# MCU.net
KiCad netlist of a schematic drawn in Altium Designer
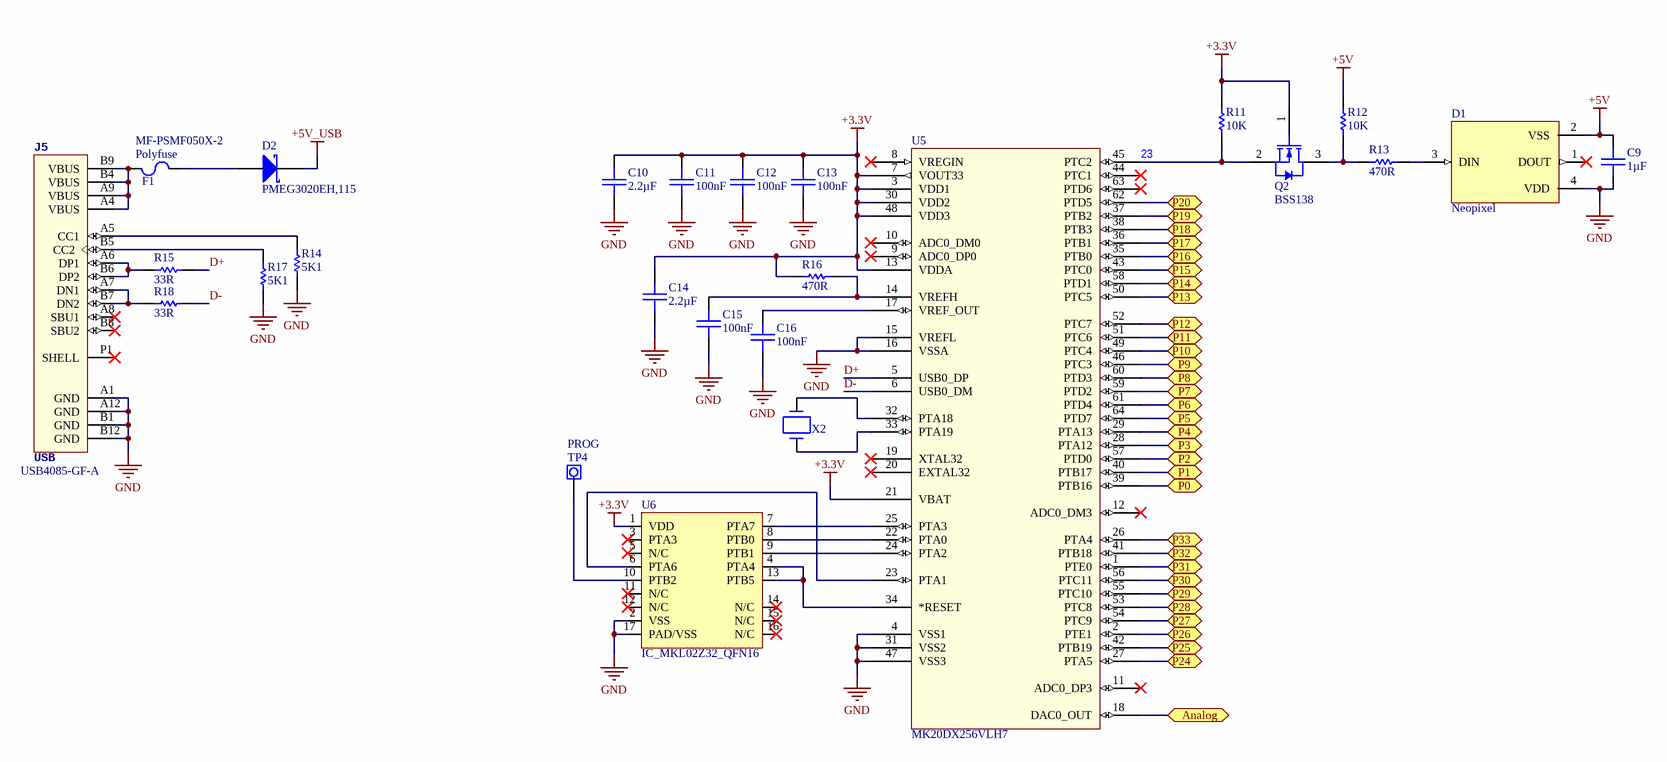
[diagram p0: MCU.SchDoc]

(export (version "E")
  (design (tool "Eeschema 10.0.6"))
  (components
    (comp (ref "C9")
      (value "1µF")
      (footprint "0603_CAP")
      (libsource (lib "Moonlight-Components") (part "Capacitor"))
    )
    (comp (ref "C10")
      (value "2.2µF")
      (footprint "0603_CAP")
      (libsource (lib "Moonlight-Components") (part "Capacitor"))
    )
    (comp (ref "C11")
      (value "100nF")
      (footprint "0603_CAP")
      (libsource (lib "Moonlight-Components") (part "Capacitor"))
    )
    (comp (ref "C12")
      (value "100nF")
      (footprint "0603_CAP")
      (libsource (lib "Moonlight-Components") (part "Capacitor"))
    )
    (comp (ref "C13")
      (value "100nF")
      (footprint "0603_CAP")
      (libsource (lib "Moonlight-Components") (part "Capacitor"))
    )
    (comp (ref "C14")
      (value "2.2µF")
      (footprint "0603_CAP")
      (libsource (lib "Moonlight-Components") (part "Capacitor"))
    )
    (comp (ref "C15")
      (value "100nF")
      (footprint "0603_CAP")
      (libsource (lib "Moonlight-Components") (part "Capacitor"))
    )
    (comp (ref "C16")
      (value "100nF")
      (footprint "0603_CAP")
      (libsource (lib "Moonlight-Components") (part "Capacitor"))
    )
    (comp (ref "D1")
      (value "Neopixel")
      (footprint "2659")
      (description "Adafruit Neopixel SMD 3535\r\nAdafruit part no. 2659\r\nDigikey part no. 1528-1542-ND")
      (fields (field (name "MP") "2659") (field (name "MF") "Adafruit Industries"))
      (libsource (lib "Moonlight-Components") (part "Neopixel"))
    )
    (comp (ref "D2")
      (value "PMEG3020EH,115")
      (footprint "SOD-123")
      (description "Digikey part no. 1727-3873-1-ND")
      (libsource (lib "Moonlight-Components") (part "Schottky diode"))
    )
    (comp (ref "F1")
      (value "Polyfuse")
      (footprint "0805")
      (description "MF-PSMF050X-2\r\nDigikey part no. MF-PSMF050X-2CT-ND")
      (libsource (lib "Moonlight-Components") (part "Fuse"))
    )
    (comp (ref "J5")
      (value "USB")
      (footprint "GCT_USB4085-GF-A_REVA")
      (description "USB 2.0 Type C Receptacle Dip Type, PCB Top Mount\r\n(Digikey part no. 2073-USB4085-GF-ACT-ND)")
      (fields (field (name "MANUFACTURER") "Global Connector Technology"))
      (libsource (lib "Moonlight-Components") (part "USB4085-GF-A_revA"))
    )
    (comp (ref "Q2")
      (value "BSS138")
      (footprint "INTR-SOT-23-3_V")
      (description "N-MOS transistor\r\nDigikey part no. BSS138CT-ND")
      (fields (field (name "MANUFACTURER") "International Rectifier"))
      (libsource (lib "Moonlight-Components") (part "IRLML2502TRPBF"))
    )
    (comp (ref "R11")
      (value "10K")
      (footprint "0603_RES")
      (libsource (lib "Moonlight-Components") (part "Resistor"))
    )
    (comp (ref "R12")
      (value "10K")
      (footprint "0603_RES")
      (libsource (lib "Moonlight-Components") (part "Resistor"))
    )
    (comp (ref "R13")
      (value "470R")
      (footprint "0603_RES")
      (libsource (lib "Moonlight-Components") (part "Resistor"))
    )
    (comp (ref "R14")
      (value "5K1")
      (footprint "0603_RES")
      (libsource (lib "Moonlight-Components") (part "Resistor"))
    )
    (comp (ref "R15")
      (value "33R")
      (footprint "0603_RES")
      (libsource (lib "Moonlight-Components") (part "Resistor"))
    )
    (comp (ref "R16")
      (value "470R")
      (footprint "0603_RES")
      (libsource (lib "Moonlight-Components") (part "Resistor"))
    )
    (comp (ref "R17")
      (value "5K1")
      (footprint "0603_RES")
      (libsource (lib "Moonlight-Components") (part "Resistor"))
    )
    (comp (ref "R18")
      (value "33R")
      (footprint "0603_RES")
      (libsource (lib "Moonlight-Components") (part "Resistor"))
    )
    (comp (ref "TP4")
      (value "PROG")
      (footprint "Testpoint2")
      (libsource (lib "Moonlight-Components") (part "Testpoint"))
    )
    (comp (ref "U5")
      (value "MK20DX256VLH7")
      (footprint "98ASS23234W_NXP")
      (description "No Description Available")
      (fields (field (name "COPYRIGHT") "Copyright (C) 2016 Accelerated Designs. All rights reserved"))
      (libsource (lib "Moonlight-Components") (part "MK20DX256VLH7"))
    )
    (comp (ref "U6")
      (value "IC_MKL02Z32_QFN16")
      (footprint "QFN50P300X300X65-17N")
      (description "Teensy bootloader")
      (fields (field (name "MP") "MKL02Z32VFG4") (field (name "MF") "NXP USA"))
      (libsource (lib "Moonlight-Components") (part "IC_MKL02Z32_QFN16"))
    )
    (comp (ref "X2")
      (value "NX3225SA-16.000000MHZ-B3")
      (footprint "XTAL_NX3225SA")
      (description "Digikey part no. 644-1099-1-ND")
      (libsource (lib "Moonlight-Components") (part "XTAL_16 MHz"))
    )
  )
  (nets
    (net (code "1") (name "+3.3V") (class "Default")
      (node (ref "C10") (pin "1") (pinfunction "1_1") (pintype "passive"))
      (node (ref "C11") (pin "1") (pinfunction "1_1") (pintype "passive"))
      (node (ref "C12") (pin "1") (pinfunction "1_1") (pintype "passive"))
      (node (ref "C13") (pin "1") (pinfunction "1_1") (pintype "passive"))
      (node (ref "C14") (pin "1") (pinfunction "1_1") (pintype "passive"))
      (node (ref "Q2") (pin "1") (pinfunction "G_1") (pintype "passive"))
      (node (ref "R11") (pin "1") (pinfunction "1_1") (pintype "passive"))
      (node (ref "R16") (pin "1") (pinfunction "1_1") (pintype "passive"))
      (node (ref "U5") (pin "13") (pinfunction "VDDA_13") (pintype "power_in"))
      (node (ref "U5") (pin "21") (pinfunction "VBAT_21") (pintype "power_in"))
      (node (ref "U5") (pin "3") (pinfunction "VDD1_3") (pintype "power_in"))
      (node (ref "U5") (pin "30") (pinfunction "VDD2_30") (pintype "power_in"))
      (node (ref "U5") (pin "48") (pinfunction "VDD3_48") (pintype "power_in"))
      (node (ref "U5") (pin "7") (pinfunction "VOUT33_7") (pintype "output"))
      (node (ref "U6") (pin "1") (pinfunction "VDD_1") (pintype "power_in"))
    )
    (net (code "2") (name "+5V") (class "Default")
      (node (ref "C9") (pin "1") (pinfunction "1_1") (pintype "passive"))
      (node (ref "D1") (pin "2") (pinfunction "VSS_2") (pintype "power_in"))
      (node (ref "R12") (pin "1") (pinfunction "1_1") (pintype "passive"))
    )
    (net (code "3") (name "+5V_USB") (class "Default")
      (node (ref "D2") (pin "2") (pinfunction "K_2") (pintype "passive"))
    )
    (net (code "4") (name "/Analog") (class "Default")
      (node (ref "U5") (pin "18") (pinfunction "DAC0_OUT_18") (pintype "bidirectional"))
    )
    (net (code "5") (name "/D+") (class "Default")
      (node (ref "R15") (pin "2") (pinfunction "2_2") (pintype "passive"))
      (node (ref "U5") (pin "5") (pinfunction "USB0_DP_5") (pintype "passive"))
    )
    (net (code "6") (name "/D-") (class "Default")
      (node (ref "R18") (pin "2") (pinfunction "2_2") (pintype "passive"))
      (node (ref "U5") (pin "6") (pinfunction "USB0_DM_6") (pintype "passive"))
    )
    (net (code "7") (name "/P0") (class "Default")
      (node (ref "U5") (pin "39") (pinfunction "PTB16_39") (pintype "bidirectional"))
    )
    (net (code "8") (name "/P1") (class "Default")
      (node (ref "U5") (pin "40") (pinfunction "PTB17_40") (pintype "bidirectional"))
    )
    (net (code "9") (name "/P2") (class "Default")
      (node (ref "U5") (pin "57") (pinfunction "PTD0_57") (pintype "bidirectional"))
    )
    (net (code "10") (name "/P3") (class "Default")
      (node (ref "U5") (pin "28") (pinfunction "PTA12_28") (pintype "bidirectional"))
    )
    (net (code "11") (name "/P4") (class "Default")
      (node (ref "U5") (pin "29") (pinfunction "PTA13_29") (pintype "bidirectional"))
    )
    (net (code "12") (name "/P5") (class "Default")
      (node (ref "U5") (pin "64") (pinfunction "PTD7_64") (pintype "bidirectional"))
    )
    (net (code "13") (name "/P6") (class "Default")
      (node (ref "U5") (pin "61") (pinfunction "PTD4_61") (pintype "bidirectional"))
    )
    (net (code "14") (name "/P7") (class "Default")
      (node (ref "U5") (pin "59") (pinfunction "PTD2_59") (pintype "bidirectional"))
    )
    (net (code "15") (name "/P8") (class "Default")
      (node (ref "U5") (pin "60") (pinfunction "PTD3_60") (pintype "bidirectional"))
    )
    (net (code "16") (name "/P9") (class "Default")
      (node (ref "U5") (pin "46") (pinfunction "PTC3_46") (pintype "bidirectional"))
    )
    (net (code "17") (name "/P10") (class "Default")
      (node (ref "U5") (pin "49") (pinfunction "PTC4_49") (pintype "bidirectional"))
    )
    (net (code "18") (name "/P11") (class "Default")
      (node (ref "U5") (pin "51") (pinfunction "PTC6_51") (pintype "bidirectional"))
    )
    (net (code "19") (name "/P12") (class "Default")
      (node (ref "U5") (pin "52") (pinfunction "PTC7_52") (pintype "bidirectional"))
    )
    (net (code "20") (name "/P13") (class "Default")
      (node (ref "U5") (pin "50") (pinfunction "PTC5_50") (pintype "bidirectional"))
    )
    (net (code "21") (name "/P14") (class "Default")
      (node (ref "U5") (pin "58") (pinfunction "PTD1_58") (pintype "bidirectional"))
    )
    (net (code "22") (name "/P15") (class "Default")
      (node (ref "U5") (pin "43") (pinfunction "PTC0_43") (pintype "bidirectional"))
    )
    (net (code "23") (name "/P16") (class "Default")
      (node (ref "U5") (pin "35") (pinfunction "PTB0_35") (pintype "bidirectional"))
    )
    (net (code "24") (name "/P17") (class "Default")
      (node (ref "U5") (pin "36") (pinfunction "PTB1_36") (pintype "bidirectional"))
    )
    (net (code "25") (name "/P18") (class "Default")
      (node (ref "U5") (pin "38") (pinfunction "PTB3_38") (pintype "bidirectional"))
    )
    (net (code "26") (name "/P19") (class "Default")
      (node (ref "U5") (pin "37") (pinfunction "PTB2_37") (pintype "bidirectional"))
    )
    (net (code "27") (name "/P20") (class "Default")
      (node (ref "U5") (pin "62") (pinfunction "PTD5_62") (pintype "bidirectional"))
    )
    (net (code "28") (name "/P24") (class "Default")
      (node (ref "U5") (pin "27") (pinfunction "PTA5_27") (pintype "bidirectional"))
    )
    (net (code "29") (name "/P25") (class "Default")
      (node (ref "U5") (pin "42") (pinfunction "PTB19_42") (pintype "bidirectional"))
    )
    (net (code "30") (name "/P26") (class "Default")
      (node (ref "U5") (pin "2") (pinfunction "PTE1_2") (pintype "bidirectional"))
    )
    (net (code "31") (name "/P27") (class "Default")
      (node (ref "U5") (pin "54") (pinfunction "PTC9_54") (pintype "bidirectional"))
    )
    (net (code "32") (name "/P28") (class "Default")
      (node (ref "U5") (pin "53") (pinfunction "PTC8_53") (pintype "bidirectional"))
    )
    (net (code "33") (name "/P29") (class "Default")
      (node (ref "U5") (pin "55") (pinfunction "PTC10_55") (pintype "bidirectional"))
    )
    (net (code "34") (name "/P30") (class "Default")
      (node (ref "U5") (pin "56") (pinfunction "PTC11_56") (pintype "bidirectional"))
    )
    (net (code "35") (name "/P31") (class "Default")
      (node (ref "U5") (pin "1") (pinfunction "PTE0_1") (pintype "bidirectional"))
    )
    (net (code "36") (name "/P32") (class "Default")
      (node (ref "U5") (pin "41") (pinfunction "PTB18_41") (pintype "bidirectional"))
    )
    (net (code "37") (name "/P33") (class "Default")
      (node (ref "U5") (pin "26") (pinfunction "PTA4_26") (pintype "bidirectional"))
    )
    (net (code "38") (name "GND") (class "Default")
      (node (ref "C10") (pin "2") (pinfunction "2_2") (pintype "passive"))
      (node (ref "C11") (pin "2") (pinfunction "2_2") (pintype "passive"))
      (node (ref "C12") (pin "2") (pinfunction "2_2") (pintype "passive"))
      (node (ref "C13") (pin "2") (pinfunction "2_2") (pintype "passive"))
      (node (ref "C14") (pin "2") (pinfunction "2_2") (pintype "passive"))
      (node (ref "C15") (pin "2") (pinfunction "2_2") (pintype "passive"))
      (node (ref "C16") (pin "2") (pinfunction "2_2") (pintype "passive"))
      (node (ref "C9") (pin "2") (pinfunction "2_2") (pintype "passive"))
      (node (ref "D1") (pin "4") (pinfunction "VDD_4") (pintype "power_in"))
      (node (ref "J5") (pin "A1") (pinfunction "GND_A1") (pintype "power_in"))
      (node (ref "J5") (pin "A12") (pinfunction "GND_A12") (pintype "power_in"))
      (node (ref "J5") (pin "B1") (pinfunction "GND_B1") (pintype "passive"))
      (node (ref "J5") (pin "B12") (pinfunction "GND_B12") (pintype "power_in"))
      (node (ref "R14") (pin "2") (pinfunction "2_2") (pintype "passive"))
      (node (ref "R17") (pin "1") (pinfunction "1_1") (pintype "passive"))
      (node (ref "U5") (pin "15") (pinfunction "VREFL_15") (pintype "power_in"))
      (node (ref "U5") (pin "16") (pinfunction "VSSA_16") (pintype "power_in"))
      (node (ref "U5") (pin "31") (pinfunction "VSS2_31") (pintype "power_in"))
      (node (ref "U5") (pin "4") (pinfunction "VSS1_4") (pintype "power_in"))
      (node (ref "U5") (pin "47") (pinfunction "VSS3_47") (pintype "power_in"))
      (node (ref "U6") (pin "17") (pinfunction "PAD/VSS_17") (pintype "power_in"))
      (node (ref "U6") (pin "2") (pinfunction "VSS_2") (pintype "power_in"))
    )
    (net (code "39") (name "Net-(D1-DIN)") (class "Default")
      (node (ref "D1") (pin "3") (pinfunction "DIN_3") (pintype "input"))
      (node (ref "R13") (pin "2") (pinfunction "2_2") (pintype "passive"))
    )
    (net (code "40") (name "Net-(D2-A)") (class "Default")
      (node (ref "D2") (pin "1") (pinfunction "A_1") (pintype "passive"))
      (node (ref "F1") (pin "2") (pinfunction "2_2") (pintype "passive"))
    )
    (net (code "41") (name "Net-(F1-Pad1)") (class "Default")
      (node (ref "F1") (pin "1") (pinfunction "1_1") (pintype "passive"))
      (node (ref "J5") (pin "A4") (pinfunction "VBUS_A4") (pintype "power_in"))
      (node (ref "J5") (pin "A9") (pinfunction "VBUS_A9") (pintype "power_in"))
      (node (ref "J5") (pin "B4") (pinfunction "VBUS_B4") (pintype "power_in"))
      (node (ref "J5") (pin "B9") (pinfunction "VBUS_B9") (pintype "power_in"))
    )
    (net (code "42") (name "Net-(J5-CC1)") (class "Default")
      (node (ref "J5") (pin "A5") (pinfunction "CC1_A5") (pintype "bidirectional"))
      (node (ref "R14") (pin "1") (pinfunction "1_1") (pintype "passive"))
    )
    (net (code "43") (name "Net-(J5-CC2)") (class "Default")
      (node (ref "J5") (pin "B5") (pinfunction "CC2_B5") (pintype "bidirectional"))
      (node (ref "R17") (pin "2") (pinfunction "2_2") (pintype "passive"))
    )
    (net (code "44") (name "Net-(J5-DN1)") (class "Default")
      (node (ref "J5") (pin "A7") (pinfunction "DN1_A7") (pintype "bidirectional"))
      (node (ref "J5") (pin "B7") (pinfunction "DN2_B7") (pintype "bidirectional"))
      (node (ref "R18") (pin "1") (pinfunction "1_1") (pintype "passive"))
    )
    (net (code "45") (name "Net-(J5-DP1)") (class "Default")
      (node (ref "J5") (pin "A6") (pinfunction "DP1_A6") (pintype "bidirectional"))
      (node (ref "J5") (pin "B6") (pinfunction "DP2_B6") (pintype "bidirectional"))
      (node (ref "R15") (pin "1") (pinfunction "1_1") (pintype "passive"))
    )
    (net (code "46") (name "Net-(Q2-D)") (class "Default")
      (node (ref "Q2") (pin "3") (pinfunction "D_3") (pintype "passive"))
      (node (ref "R12") (pin "2") (pinfunction "2_2") (pintype "passive"))
      (node (ref "R13") (pin "1") (pinfunction "1_1") (pintype "passive"))
    )
    (net (code "47") (name "Net-(Q2-S)") (class "Default")
      (node (ref "Q2") (pin "2") (pinfunction "S_2") (pintype "passive"))
      (node (ref "R11") (pin "2") (pinfunction "2_2") (pintype "passive"))
      (node (ref "U5") (pin "45") (pinfunction "PTC2_45") (pintype "bidirectional"))
    )
    (net (code "48") (name "Net-(U5-*RESET)") (class "Default")
      (node (ref "U5") (pin "34") (pinfunction "*RESET_34") (pintype "passive"))
      (node (ref "U6") (pin "13") (pinfunction "PTB5_13") (pintype "bidirectional"))
      (node (ref "U6") (pin "4") (pinfunction "PTA4_4") (pintype "bidirectional"))
    )
    (net (code "49") (name "Net-(U5-PTA0)") (class "Default")
      (node (ref "U5") (pin "22") (pinfunction "PTA0_22") (pintype "bidirectional"))
      (node (ref "U6") (pin "8") (pinfunction "PTB0_8") (pintype "bidirectional"))
    )
    (net (code "50") (name "Net-(U5-PTA1)") (class "Default")
      (node (ref "U5") (pin "23") (pinfunction "PTA1_23") (pintype "bidirectional"))
      (node (ref "U6") (pin "6") (pinfunction "PTA6_6") (pintype "bidirectional"))
    )
    (net (code "51") (name "Net-(U5-PTA2)") (class "Default")
      (node (ref "U5") (pin "24") (pinfunction "PTA2_24") (pintype "bidirectional"))
      (node (ref "U6") (pin "9") (pinfunction "PTB1_9") (pintype "bidirectional"))
    )
    (net (code "52") (name "Net-(U5-PTA3)") (class "Default")
      (node (ref "U5") (pin "25") (pinfunction "PTA3_25") (pintype "bidirectional"))
      (node (ref "U6") (pin "7") (pinfunction "PTA7_7") (pintype "bidirectional"))
    )
    (net (code "53") (name "Net-(U5-PTA18)") (class "Default")
      (node (ref "U5") (pin "32") (pinfunction "PTA18_32") (pintype "bidirectional"))
      (node (ref "X2") (pin "3") (pinfunction "3_3") (pintype "passive"))
    )
    (net (code "54") (name "Net-(U5-PTA19)") (class "Default")
      (node (ref "U5") (pin "33") (pinfunction "PTA19_33") (pintype "bidirectional"))
      (node (ref "X2") (pin "1") (pinfunction "1_1") (pintype "passive"))
    )
    (net (code "55") (name "Net-(U5-VREFH)") (class "Default")
      (node (ref "C15") (pin "1") (pinfunction "1_1") (pintype "passive"))
      (node (ref "R16") (pin "2") (pinfunction "2_2") (pintype "passive"))
      (node (ref "U5") (pin "14") (pinfunction "VREFH_14") (pintype "power_in"))
    )
    (net (code "56") (name "Net-(U5-VREF_OUT)") (class "Default")
      (node (ref "C16") (pin "1") (pinfunction "1_1") (pintype "passive"))
      (node (ref "U5") (pin "17") (pinfunction "VREF_OUT_17") (pintype "bidirectional"))
    )
    (net (code "57") (name "Net-(U6-PTB2)") (class "Default")
      (node (ref "TP4") (pin "1") (pinfunction "1_1") (pintype "passive"))
      (node (ref "U6") (pin "10") (pinfunction "PTB2_10") (pintype "bidirectional"))
    )
    (net (code "58") (name "unconnected-(D1-DOUT-Pad1)") (class "Default")
      (node (ref "D1") (pin "1") (pinfunction "DOUT_1") (pintype "output+no_connect"))
    )
    (net (code "59") (name "unconnected-(J5-SBU1-PadA8)") (class "Default")
      (node (ref "J5") (pin "A8") (pinfunction "SBU1_A8") (pintype "bidirectional+no_connect"))
    )
    (net (code "60") (name "unconnected-(J5-SBU2-PadB8)") (class "Default")
      (node (ref "J5") (pin "B8") (pinfunction "SBU2_B8") (pintype "bidirectional+no_connect"))
    )
    (net (code "61") (name "unconnected-(J5-SHELL-PadP1)") (class "Default")
      (node (ref "J5") (pin "P1") (pinfunction "SHELL_P1") (pintype "passive+no_connect"))
    )
    (net (code "62") (name "unconnected-(U5-ADC0_DM0-Pad10)") (class "Default")
      (node (ref "U5") (pin "10") (pinfunction "ADC0_DM0_10") (pintype "bidirectional+no_connect"))
    )
    (net (code "63") (name "unconnected-(U5-ADC0_DM3-Pad12)") (class "Default")
      (node (ref "U5") (pin "12") (pinfunction "ADC0_DM3_12") (pintype "bidirectional+no_connect"))
    )
    (net (code "64") (name "unconnected-(U5-ADC0_DP0-Pad9)") (class "Default")
      (node (ref "U5") (pin "9") (pinfunction "ADC0_DP0_9") (pintype "bidirectional+no_connect"))
    )
    (net (code "65") (name "unconnected-(U5-ADC0_DP3-Pad11)") (class "Default")
      (node (ref "U5") (pin "11") (pinfunction "ADC0_DP3_11") (pintype "bidirectional+no_connect"))
    )
    (net (code "66") (name "unconnected-(U5-EXTAL32-Pad20)") (class "Default")
      (node (ref "U5") (pin "20") (pinfunction "EXTAL32_20") (pintype "passive+no_connect"))
    )
    (net (code "67") (name "unconnected-(U5-PTC1-Pad44)") (class "Default")
      (node (ref "U5") (pin "44") (pinfunction "PTC1_44") (pintype "bidirectional+no_connect"))
    )
    (net (code "68") (name "unconnected-(U5-PTD6-Pad63)") (class "Default")
      (node (ref "U5") (pin "63") (pinfunction "PTD6_63") (pintype "bidirectional+no_connect"))
    )
    (net (code "69") (name "unconnected-(U5-VREGIN-Pad8)") (class "Default")
      (node (ref "U5") (pin "8") (pinfunction "VREGIN_8") (pintype "input+no_connect"))
    )
    (net (code "70") (name "unconnected-(U5-XTAL32-Pad19)") (class "Default")
      (node (ref "U5") (pin "19") (pinfunction "XTAL32_19") (pintype "passive+no_connect"))
    )
    (net (code "71") (name "unconnected-(U6-N{slash}C-Pad5)") (class "Default")
      (node (ref "U6") (pin "5") (pinfunction "N/C_5") (pintype "bidirectional+no_connect"))
    )
    (net (code "72") (name "unconnected-(U6-N{slash}C-Pad11)") (class "Default")
      (node (ref "U6") (pin "11") (pinfunction "N/C_11") (pintype "bidirectional+no_connect"))
    )
    (net (code "73") (name "unconnected-(U6-N{slash}C-Pad12)") (class "Default")
      (node (ref "U6") (pin "12") (pinfunction "N/C_12") (pintype "bidirectional+no_connect"))
    )
    (net (code "74") (name "unconnected-(U6-N{slash}C-Pad14)") (class "Default")
      (node (ref "U6") (pin "14") (pinfunction "N/C_14") (pintype "bidirectional+no_connect"))
    )
    (net (code "75") (name "unconnected-(U6-N{slash}C-Pad15)") (class "Default")
      (node (ref "U6") (pin "15") (pinfunction "N/C_15") (pintype "bidirectional+no_connect"))
    )
    (net (code "76") (name "unconnected-(U6-N{slash}C-Pad16)") (class "Default")
      (node (ref "U6") (pin "16") (pinfunction "N/C_16") (pintype "bidirectional+no_connect"))
    )
    (net (code "77") (name "unconnected-(U6-PTA3-Pad3)") (class "Default")
      (node (ref "U6") (pin "3") (pinfunction "PTA3_3") (pintype "bidirectional+no_connect"))
    )
  )
)
